# arcade-X.net
KiCad netlist of a schematic drawn in EAGLE
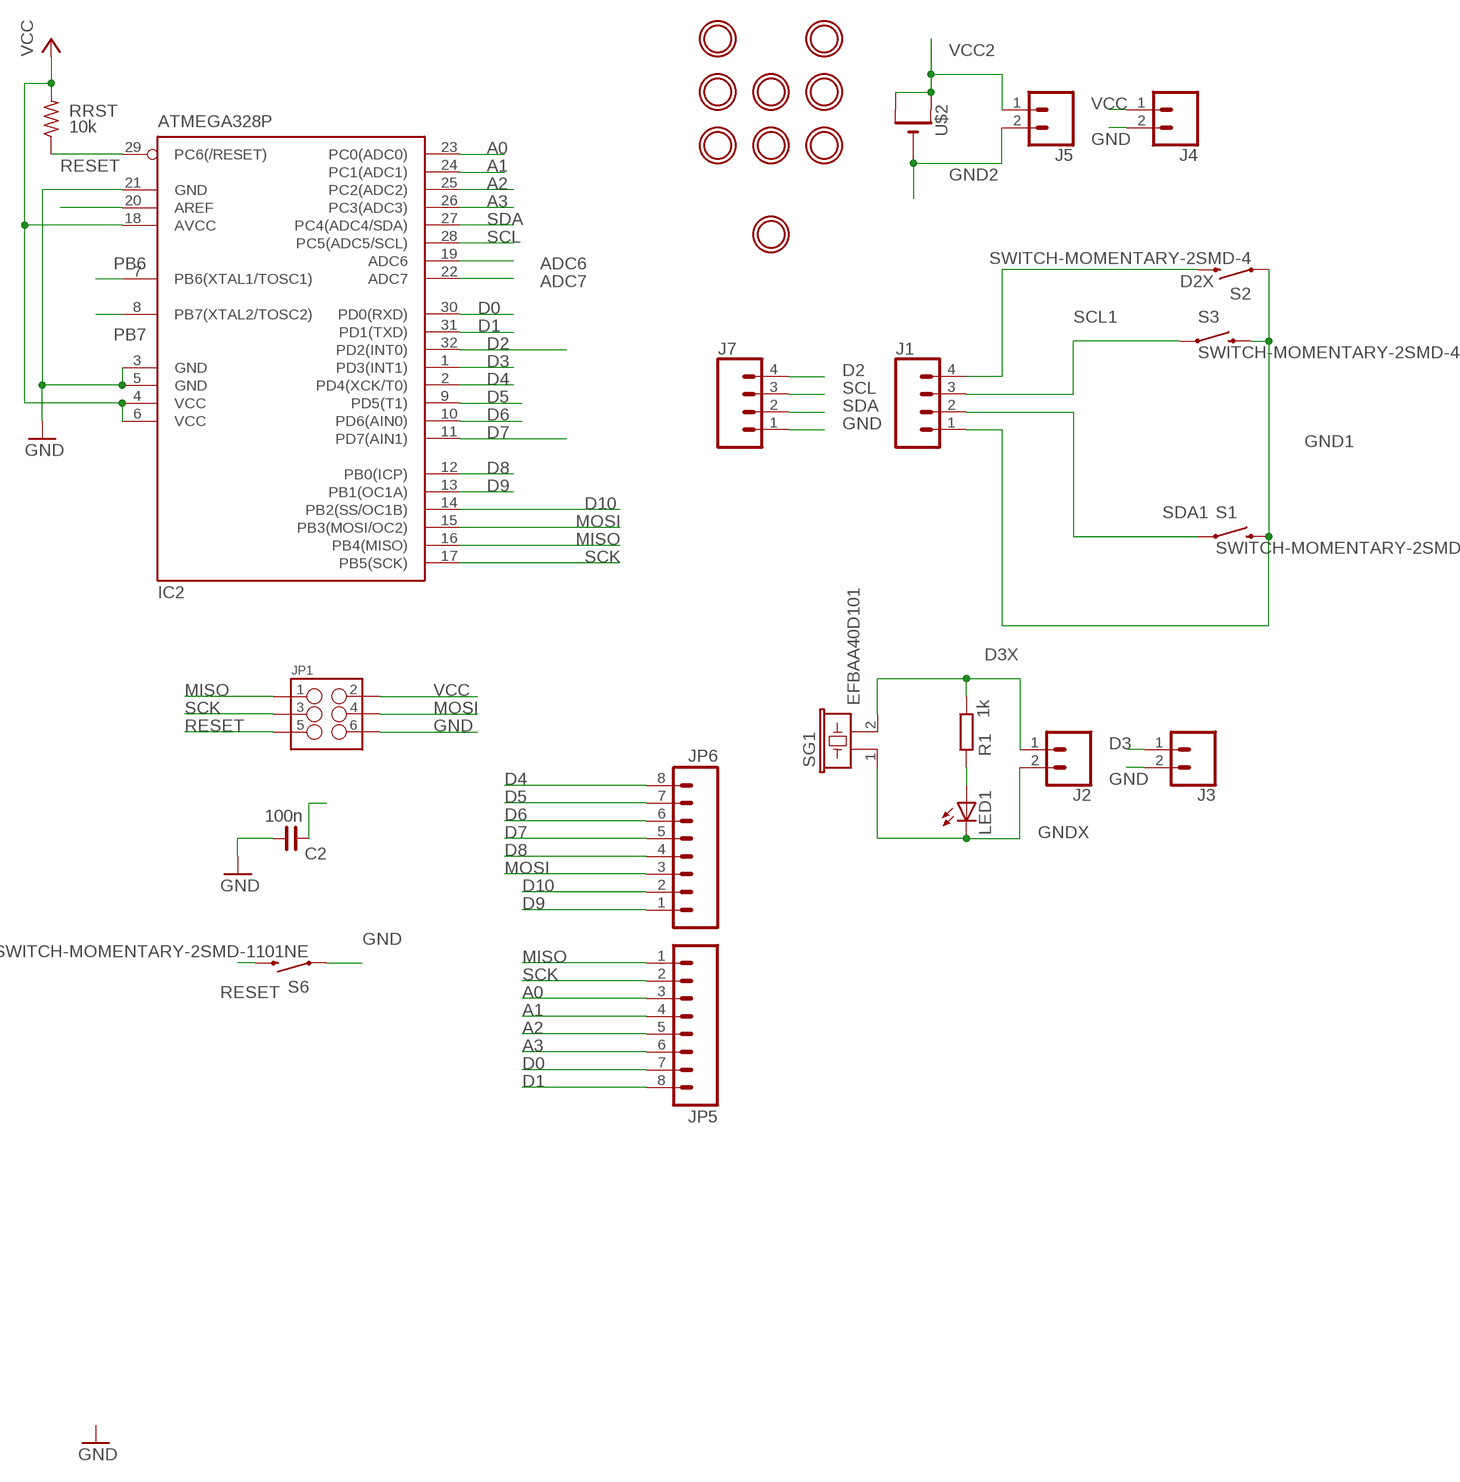
[diagram p0: schematic, sheet 1]

(export (version "E")
  (design (tool "Eeschema 10.0.6"))
  (components
    (comp (ref "C2")
      (value "100n")
      (footprint "eagle-import:C0805")
      (libsource (lib "eagle-import") (part "C_0805"))
    )
    (comp (ref "IC2")
      (value "ATMEGA328P")
      (footprint "eagle-import:TQFP32-08")
      (fields (field (name "MPN") "ATMEGA8-16AU"))
      (libsource (lib "eagle-import") (part "MEGA8-AI"))
    )
    (comp (ref "J1")
      (value "CONN_04LONGPADS")
      (footprint "eagle-import:1X04_LONGPADS")
      (libsource (lib "eagle-import") (part "CONN_04LONGPADS"))
    )
    (comp (ref "J2")
      (value "CONN_02PTH3")
      (footprint "eagle-import:1X02_LONGPADS")
      (libsource (lib "eagle-import") (part "CONN_02PTH3"))
    )
    (comp (ref "J3")
      (value "CONN_02PTH3")
      (footprint "eagle-import:1X02_LONGPADS")
      (libsource (lib "eagle-import") (part "CONN_02PTH3"))
    )
    (comp (ref "J4")
      (value "CONN_02PTH3")
      (footprint "eagle-import:1X02_LONGPADS")
      (libsource (lib "eagle-import") (part "CONN_02PTH3"))
    )
    (comp (ref "J5")
      (value "CONN_02PTH3")
      (footprint "eagle-import:1X02_LONGPADS")
      (libsource (lib "eagle-import") (part "CONN_02PTH3"))
    )
    (comp (ref "J7")
      (value "CONN_04LONGPADS")
      (footprint "eagle-import:1X04_LONGPADS")
      (libsource (lib "eagle-import") (part "CONN_04LONGPADS"))
    )
    (comp (ref "JP1")
      (value "M03X2NO_SILK")
      (footprint "eagle-import:2X3-NS")
      (libsource (lib "eagle-import") (part "M03X2NO_SILK"))
    )
    (comp (ref "JP5")
      (value "M08NO_SILK")
      (footprint "eagle-import:1X08_PIN1_NO_SILK")
      (libsource (lib "eagle-import") (part "M08NO_SILK"))
    )
    (comp (ref "JP6")
      (value "M08NO_SILK")
      (footprint "eagle-import:1X08_PIN1_NO_SILK")
      (libsource (lib "eagle-import") (part "M08NO_SILK"))
    )
    (comp (ref "LED1")
      (value "LED3MM")
      (footprint "eagle-import:LED3MM")
      (libsource (lib "eagle-import") (part "LED3MM"))
    )
    (comp (ref "R1")
      (value "1k")
      (footprint "eagle-import:R0805")
      (libsource (lib "eagle-import") (part "R-EU_R0805"))
    )
    (comp (ref "RRST")
      (value "10k")
      (footprint "eagle-import:R0805@1")
      (libsource (lib "eagle-import") (part "R-US_R0805"))
    )
    (comp (ref "S1")
      (value "SWITCH-MOMENTARY-2SMD-4")
      (footprint "eagle-import:TACTILE_SWITCH_TALL")
      (libsource (lib "eagle-import") (part "SWITCH-MOMENTARY-2SMD-4"))
    )
    (comp (ref "S2")
      (value "SWITCH-MOMENTARY-2SMD-4")
      (footprint "eagle-import:TACTILE_SWITCH_TALL")
      (libsource (lib "eagle-import") (part "SWITCH-MOMENTARY-2SMD-4"))
    )
    (comp (ref "S3")
      (value "SWITCH-MOMENTARY-2SMD-4")
      (footprint "eagle-import:TACTILE_SWITCH_TALL")
      (libsource (lib "eagle-import") (part "SWITCH-MOMENTARY-2SMD-4"))
    )
    (comp (ref "S6")
      (value "SWITCH-MOMENTARY-2SMD-1101NE")
      (footprint "eagle-import:TACTILE-SWITCH-1101NE")
      (libsource (lib "eagle-import") (part "SWITCH-MOMENTARY-2SMD-1101NE"))
    )
    (comp (ref "SG1")
      (value "EFBAA40D101")
      (footprint "eagle-import:EFBAA40D101")
      (libsource (lib "eagle-import") (part "EFB?AA40D101"))
    )
    (comp (ref "U$1")
      (value "MOUNTINGHOLE3.0THIN")
      (footprint "eagle-import:MOUNTINGHOLE_3.0_PLATEDTHIN")
      (libsource (lib "eagle-import") (part "MOUNTINGHOLE3.0THIN"))
    )
    (comp (ref "U$2")
      (value "CR2032THM")
      (footprint "eagle-import:CR2032-THRU")
      (libsource (lib "eagle-import") (part "CR2032THM"))
    )
    (comp (ref "U$3")
      (value "MOUNTINGHOLE2.0")
      (footprint "eagle-import:MOUNTINGHOLE_2.0_PLATED")
      (libsource (lib "eagle-import") (part "MOUNTINGHOLE2.0"))
    )
    (comp (ref "U$4")
      (value "MOUNTINGHOLE2.0")
      (footprint "eagle-import:MOUNTINGHOLE_2.0_PLATED")
      (libsource (lib "eagle-import") (part "MOUNTINGHOLE2.0"))
    )
    (comp (ref "U$5")
      (value "MOUNTINGHOLE2.0")
      (footprint "eagle-import:MOUNTINGHOLE_2.0_PLATED")
      (libsource (lib "eagle-import") (part "MOUNTINGHOLE2.0"))
    )
    (comp (ref "U$7")
      (value "MOUNTINGHOLE2.0")
      (footprint "eagle-import:MOUNTINGHOLE_2.0_PLATED")
      (libsource (lib "eagle-import") (part "MOUNTINGHOLE2.0"))
    )
    (comp (ref "U$8")
      (value "MOUNTINGHOLE2.0")
      (footprint "eagle-import:MOUNTINGHOLE_2.0_PLATED")
      (libsource (lib "eagle-import") (part "MOUNTINGHOLE2.0"))
    )
    (comp (ref "U$9")
      (value "MOUNTINGHOLE2.0")
      (footprint "eagle-import:MOUNTINGHOLE_2.0_PLATED")
      (libsource (lib "eagle-import") (part "MOUNTINGHOLE2.0"))
    )
    (comp (ref "U$10")
      (value "MOUNTINGHOLE2.0")
      (footprint "eagle-import:MOUNTINGHOLE_2.0_PLATED")
      (libsource (lib "eagle-import") (part "MOUNTINGHOLE2.0"))
    )
    (comp (ref "U$11")
      (value "MOUNTINGHOLE2.0")
      (footprint "eagle-import:MOUNTINGHOLE_2.0_PLATED")
      (libsource (lib "eagle-import") (part "MOUNTINGHOLE2.0"))
    )
  )
  (nets
    (net (code "1") (name "/A0") (class "Default")
      (node (ref "IC2") (pin "23") (pinfunction "PC0(ADC0)_23") (pintype "bidirectional"))
      (node (ref "JP5") (pin "3") (pinfunction "3_3") (pintype "passive"))
    )
    (net (code "2") (name "/A1") (class "Default")
      (node (ref "IC2") (pin "24") (pinfunction "PC1(ADC1)_24") (pintype "bidirectional"))
      (node (ref "JP5") (pin "4") (pinfunction "4_4") (pintype "passive"))
    )
    (net (code "3") (name "/A2") (class "Default")
      (node (ref "IC2") (pin "25") (pinfunction "PC2(ADC2)_25") (pintype "bidirectional"))
      (node (ref "JP5") (pin "5") (pinfunction "5_5") (pintype "passive"))
    )
    (net (code "4") (name "/A3") (class "Default")
      (node (ref "IC2") (pin "26") (pinfunction "PC3(ADC3)_26") (pintype "bidirectional"))
      (node (ref "JP5") (pin "6") (pinfunction "6_6") (pintype "passive"))
    )
    (net (code "5") (name "/ADC6") (class "Default")
      (node (ref "IC2") (pin "19") (pinfunction "ADC6_19") (pintype "bidirectional"))
    )
    (net (code "6") (name "/ADC7") (class "Default")
      (node (ref "IC2") (pin "22") (pinfunction "ADC7_22") (pintype "bidirectional"))
    )
    (net (code "7") (name "/D0") (class "Default")
      (node (ref "IC2") (pin "30") (pinfunction "PD0(RXD)_30") (pintype "bidirectional"))
      (node (ref "JP5") (pin "7") (pinfunction "7_7") (pintype "passive"))
    )
    (net (code "8") (name "/D1") (class "Default")
      (node (ref "IC2") (pin "31") (pinfunction "PD1(TXD)_31") (pintype "bidirectional"))
      (node (ref "JP5") (pin "8") (pinfunction "8_8") (pintype "passive"))
    )
    (net (code "9") (name "/D2") (class "Default")
      (node (ref "IC2") (pin "32") (pinfunction "PD2(INT0)_32") (pintype "bidirectional"))
      (node (ref "J7") (pin "4") (pinfunction "4_4") (pintype "passive"))
    )
    (net (code "10") (name "/D2X") (class "Default")
      (node (ref "J1") (pin "4") (pinfunction "4_4") (pintype "passive"))
      (node (ref "S2") (pin "B2") (pinfunction "2_B2") (pintype "passive"))
    )
    (net (code "11") (name "/D3") (class "Default")
      (node (ref "IC2") (pin "1") (pinfunction "PD3(INT1)_1") (pintype "bidirectional"))
      (node (ref "J3") (pin "1") (pinfunction "1_1") (pintype "passive"))
    )
    (net (code "12") (name "/D3X") (class "Default")
      (node (ref "J2") (pin "1") (pinfunction "1_1") (pintype "passive"))
      (node (ref "R1") (pin "1") (pinfunction "1_1") (pintype "passive"))
      (node (ref "SG1") (pin "2") (pinfunction "2_2") (pintype "passive"))
    )
    (net (code "13") (name "/D4") (class "Default")
      (node (ref "IC2") (pin "2") (pinfunction "PD4(XCK/T0)_2") (pintype "bidirectional"))
      (node (ref "JP6") (pin "8") (pinfunction "8_8") (pintype "passive"))
    )
    (net (code "14") (name "/D5") (class "Default")
      (node (ref "IC2") (pin "9") (pinfunction "PD5(T1)_9") (pintype "bidirectional"))
      (node (ref "JP6") (pin "7") (pinfunction "7_7") (pintype "passive"))
    )
    (net (code "15") (name "/D6") (class "Default")
      (node (ref "IC2") (pin "10") (pinfunction "PD6(AIN0)_10") (pintype "bidirectional"))
      (node (ref "JP6") (pin "6") (pinfunction "6_6") (pintype "passive"))
    )
    (net (code "16") (name "/D7") (class "Default")
      (node (ref "IC2") (pin "11") (pinfunction "PD7(AIN1)_11") (pintype "bidirectional"))
      (node (ref "JP6") (pin "5") (pinfunction "5_5") (pintype "passive"))
    )
    (net (code "17") (name "/D8") (class "Default")
      (node (ref "IC2") (pin "12") (pinfunction "PB0(ICP)_12") (pintype "bidirectional"))
      (node (ref "JP6") (pin "4") (pinfunction "4_4") (pintype "passive"))
    )
    (net (code "18") (name "/D9") (class "Default")
      (node (ref "IC2") (pin "13") (pinfunction "PB1(OC1A)_13") (pintype "bidirectional"))
      (node (ref "JP6") (pin "1") (pinfunction "1_1") (pintype "passive"))
    )
    (net (code "19") (name "/D10") (class "Default")
      (node (ref "IC2") (pin "14") (pinfunction "PB2(SS/OC1B)_14") (pintype "bidirectional"))
      (node (ref "JP6") (pin "2") (pinfunction "2_2") (pintype "passive"))
    )
    (net (code "20") (name "/GND1") (class "Default")
      (node (ref "J1") (pin "1") (pinfunction "1_1") (pintype "passive"))
      (node (ref "S1") (pin "B2") (pinfunction "2_B2") (pintype "passive"))
      (node (ref "S2") (pin "A2") (pinfunction "1_A2") (pintype "passive"))
      (node (ref "S3") (pin "B2") (pinfunction "2_B2") (pintype "passive"))
    )
    (net (code "21") (name "/GND2") (class "Default")
      (node (ref "J5") (pin "2") (pinfunction "2_2") (pintype "passive"))
      (node (ref "U$2") (pin "-") (pinfunction "-_-") (pintype "passive"))
    )
    (net (code "22") (name "/GNDX") (class "Default")
      (node (ref "J2") (pin "2") (pinfunction "2_2") (pintype "passive"))
      (node (ref "LED1") (pin "K") (pinfunction "C_K") (pintype "passive"))
      (node (ref "SG1") (pin "1") (pinfunction "1_1") (pintype "passive"))
    )
    (net (code "23") (name "/MISO") (class "Default")
      (node (ref "IC2") (pin "16") (pinfunction "PB4(MISO)_16") (pintype "bidirectional"))
      (node (ref "JP1") (pin "1") (pinfunction "1_1") (pintype "bidirectional"))
      (node (ref "JP5") (pin "1") (pinfunction "1_1") (pintype "passive"))
    )
    (net (code "24") (name "/MOSI") (class "Default")
      (node (ref "IC2") (pin "15") (pinfunction "PB3(MOSI/OC2)_15") (pintype "bidirectional"))
      (node (ref "JP1") (pin "4") (pinfunction "4_4") (pintype "bidirectional"))
      (node (ref "JP6") (pin "3") (pinfunction "3_3") (pintype "passive"))
    )
    (net (code "25") (name "/PB6") (class "Default")
      (node (ref "IC2") (pin "7") (pinfunction "PB6(XTAL1/TOSC1)_7") (pintype "bidirectional"))
    )
    (net (code "26") (name "/PB7") (class "Default")
      (node (ref "IC2") (pin "8") (pinfunction "PB7(XTAL2/TOSC2)_8") (pintype "bidirectional"))
    )
    (net (code "27") (name "/RESET") (class "Default")
      (node (ref "IC2") (pin "29") (pinfunction "PC6(/RESET)_29") (pintype "bidirectional"))
      (node (ref "JP1") (pin "5") (pinfunction "5_5") (pintype "bidirectional"))
      (node (ref "RRST") (pin "1") (pinfunction "1_1") (pintype "passive"))
      (node (ref "S6") (pin "2") (pinfunction "2_2") (pintype "passive"))
    )
    (net (code "28") (name "/SCK") (class "Default")
      (node (ref "IC2") (pin "17") (pinfunction "PB5(SCK)_17") (pintype "bidirectional"))
      (node (ref "JP1") (pin "3") (pinfunction "3_3") (pintype "bidirectional"))
      (node (ref "JP5") (pin "2") (pinfunction "2_2") (pintype "passive"))
    )
    (net (code "29") (name "/SCL") (class "Default")
      (node (ref "IC2") (pin "28") (pinfunction "PC5(ADC5/SCL)_28") (pintype "bidirectional"))
      (node (ref "J7") (pin "3") (pinfunction "3_3") (pintype "passive"))
    )
    (net (code "30") (name "/SCL1") (class "Default")
      (node (ref "J1") (pin "3") (pinfunction "3_3") (pintype "passive"))
      (node (ref "S3") (pin "A2") (pinfunction "1_A2") (pintype "passive"))
    )
    (net (code "31") (name "/SDA") (class "Default")
      (node (ref "IC2") (pin "27") (pinfunction "PC4(ADC4/SDA)_27") (pintype "bidirectional"))
      (node (ref "J7") (pin "2") (pinfunction "2_2") (pintype "passive"))
    )
    (net (code "32") (name "/SDA1") (class "Default")
      (node (ref "J1") (pin "2") (pinfunction "2_2") (pintype "passive"))
      (node (ref "S1") (pin "A2") (pinfunction "1_A2") (pintype "passive"))
    )
    (net (code "33") (name "/VCC2") (class "Default")
      (node (ref "J5") (pin "1") (pinfunction "1_1") (pintype "passive"))
      (node (ref "U$2") (pin "+1") (pinfunction "+_+1") (pintype "passive"))
      (node (ref "U$2") (pin "+2") (pinfunction "+1_+2") (pintype "passive"))
    )
    (net (code "34") (name "GND") (class "Default")
      (node (ref "C2") (pin "1") (pinfunction "1_1") (pintype "passive"))
      (node (ref "IC2") (pin "21") (pinfunction "GND_21") (pintype "power_in"))
      (node (ref "IC2") (pin "3") (pinfunction "GND_3") (pintype "power_in"))
      (node (ref "IC2") (pin "5") (pinfunction "GND_5") (pintype "power_in"))
      (node (ref "J3") (pin "2") (pinfunction "2_2") (pintype "passive"))
      (node (ref "J4") (pin "2") (pinfunction "2_2") (pintype "passive"))
      (node (ref "J7") (pin "1") (pinfunction "1_1") (pintype "passive"))
      (node (ref "JP1") (pin "6") (pinfunction "6_6") (pintype "bidirectional"))
      (node (ref "S6") (pin "1") (pinfunction "1_1") (pintype "passive"))
    )
    (net (code "35") (name "Net-(LED1-PadA)") (class "Default")
      (node (ref "LED1") (pin "A") (pinfunction "A_A") (pintype "passive"))
      (node (ref "R1") (pin "2") (pinfunction "2_2") (pintype "passive"))
    )
    (net (code "36") (name "VCC") (class "Default")
      (node (ref "C2") (pin "2") (pinfunction "2_2") (pintype "passive"))
      (node (ref "IC2") (pin "18") (pinfunction "AVCC_18") (pintype "power_in"))
      (node (ref "IC2") (pin "4") (pinfunction "VCC_4") (pintype "power_in"))
      (node (ref "IC2") (pin "6") (pinfunction "VCC_6") (pintype "power_in"))
      (node (ref "J4") (pin "1") (pinfunction "1_1") (pintype "passive"))
      (node (ref "JP1") (pin "2") (pinfunction "2_2") (pintype "bidirectional"))
      (node (ref "RRST") (pin "2") (pinfunction "2_2") (pintype "passive"))
    )
    (net (code "37") (name "unconnected-(IC2-AREF-Pad20)") (class "Default")
      (node (ref "IC2") (pin "20") (pinfunction "AREF_20") (pintype "passive"))
    )
  )
)
